# nivel0.net
KiCad netlist of a schematic drawn in EAGLE
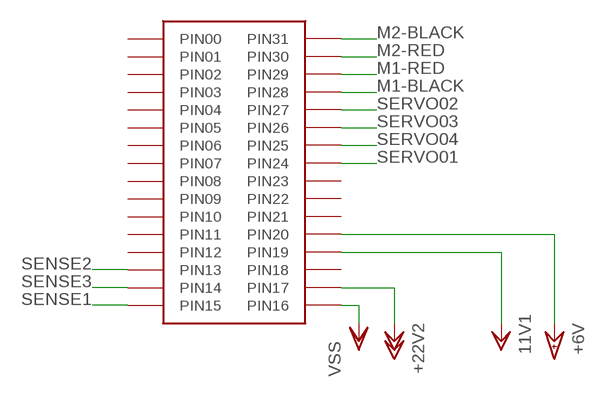
[diagram p0: schematic, sheet 1]
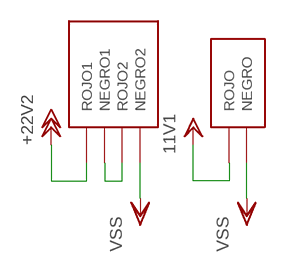
[diagram p1: schematic, sheet 2]
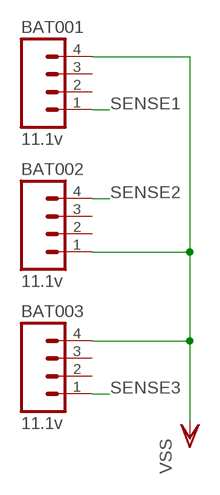
[diagram p2: schematic, sheet 3]
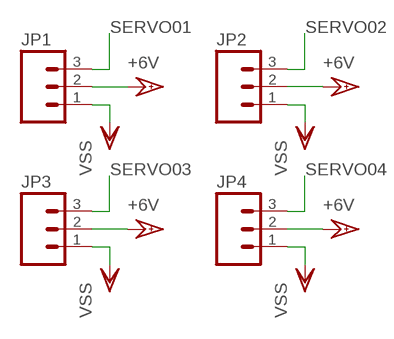
[diagram p3: schematic, sheet 4]
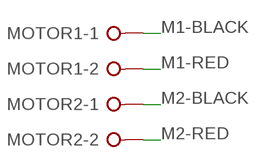
[diagram p4: schematic, sheet 5]

(export (version "E")
  (design (tool "Eeschema 10.0.6"))
  (components
    (comp (ref "U$11")
      (value "CONECTOR_AUDIO")
      (footprint "eagle-import:CONECTOR_AUDIO")
      (libsource (lib "eagle-import") (part "CONECTOR_AUDIO"))
    )
    (comp (ref "U$12")
      (value "CONECTOR_AUDIO2")
      (footprint "eagle-import:CONECTOR_AUDIO2")
      (libsource (lib "eagle-import") (part "CONECTOR_AUDIO2"))
    )
    (comp (ref "U$1")
      (value "BASE")
      (footprint "eagle-import:BASE")
      (libsource (lib "eagle-import") (part "BASE"))
    )
    (comp (ref "JP1")
      (value "M03LONGPADS")
      (footprint "eagle-import:1X03_LONGPADS")
      (libsource (lib "eagle-import") (part "M03LONGPADS"))
    )
    (comp (ref "JP2")
      (value "M03LONGPADS")
      (footprint "eagle-import:1X03_LONGPADS")
      (libsource (lib "eagle-import") (part "M03LONGPADS"))
    )
    (comp (ref "JP3")
      (value "M03LONGPADS")
      (footprint "eagle-import:1X03_LONGPADS")
      (libsource (lib "eagle-import") (part "M03LONGPADS"))
    )
    (comp (ref "JP4")
      (value "M03LONGPADS")
      (footprint "eagle-import:1X03_LONGPADS")
      (libsource (lib "eagle-import") (part "M03LONGPADS"))
    )
    (comp (ref "MOTOR1")
      (value "W237-02P")
      (footprint "eagle-import:W237-132")
      (libsource (lib "eagle-import") (part "W237-02P"))
    )
    (comp (ref "MOTOR2")
      (value "W237-02P")
      (footprint "eagle-import:W237-132")
      (libsource (lib "eagle-import") (part "W237-02P"))
    )
    (comp (ref "BAT001")
      (value "11.1v")
      (footprint "eagle-import:1X04_LONGPADS")
      (libsource (lib "eagle-import") (part "M04LONGPADS"))
    )
    (comp (ref "BAT002")
      (value "11.1v")
      (footprint "eagle-import:1X04_LONGPADS")
      (libsource (lib "eagle-import") (part "M04LONGPADS"))
    )
    (comp (ref "BAT003")
      (value "11.1v")
      (footprint "eagle-import:1X04_LONGPADS")
      (libsource (lib "eagle-import") (part "M04LONGPADS"))
    )
  )
  (nets
    (net (code "1") (name "+6V") (class "Default")
      (node (ref "JP1") (pin "2") (pinfunction "2_2") (pintype "passive"))
      (node (ref "JP2") (pin "2") (pinfunction "2_2") (pintype "passive"))
      (node (ref "JP3") (pin "2") (pinfunction "2_2") (pintype "passive"))
      (node (ref "JP4") (pin "2") (pinfunction "2_2") (pintype "passive"))
      (node (ref "U$1") (pin "PIN20") (pinfunction "PIN20_PIN20") (pintype "bidirectional"))
    )
    (net (code "2") (name "+11V1") (class "Default")
      (node (ref "U$1") (pin "PIN19") (pinfunction "PIN19_PIN19") (pintype "bidirectional"))
      (node (ref "U$12") (pin "P$2") (pinfunction "ROJO_P$2") (pintype "bidirectional"))
    )
    (net (code "3") (name "+22V") (class "Default")
      (node (ref "U$1") (pin "PIN17") (pinfunction "PIN17_PIN17") (pintype "bidirectional"))
      (node (ref "U$11") (pin "P$1") (pinfunction "ROJO1_P$1") (pintype "bidirectional"))
    )
    (net (code "4") (name "M1-BLACK") (class "Default")
      (node (ref "MOTOR1") (pin "1") (pinfunction "KL_1") (pintype "passive"))
      (node (ref "U$1") (pin "PIN28") (pinfunction "PIN28_PIN28") (pintype "bidirectional"))
    )
    (net (code "5") (name "M1-RED") (class "Default")
      (node (ref "MOTOR1") (pin "2") (pinfunction "KL_2") (pintype "passive"))
      (node (ref "U$1") (pin "PIN29") (pinfunction "PIN29_PIN29") (pintype "bidirectional"))
    )
    (net (code "6") (name "M2-BLACK") (class "Default")
      (node (ref "MOTOR2") (pin "1") (pinfunction "KL_1") (pintype "passive"))
      (node (ref "U$1") (pin "PIN31") (pinfunction "PIN31_PIN31") (pintype "bidirectional"))
    )
    (net (code "7") (name "M2-RED") (class "Default")
      (node (ref "MOTOR2") (pin "2") (pinfunction "KL_2") (pintype "passive"))
      (node (ref "U$1") (pin "PIN30") (pinfunction "PIN30_PIN30") (pintype "bidirectional"))
    )
    (net (code "8") (name "Net-(U$11-NEGRO1)") (class "Default")
      (node (ref "U$11") (pin "P$2") (pinfunction "NEGRO1_P$2") (pintype "bidirectional"))
      (node (ref "U$11") (pin "P$3") (pinfunction "ROJO2_P$3") (pintype "bidirectional"))
    )
    (net (code "9") (name "SENSE1") (class "Default")
      (node (ref "BAT001") (pin "1") (pinfunction "1_1") (pintype "passive"))
      (node (ref "U$1") (pin "PIN15") (pinfunction "PIN15_PIN15") (pintype "bidirectional"))
    )
    (net (code "10") (name "SENSE2") (class "Default")
      (node (ref "BAT002") (pin "4") (pinfunction "4_4") (pintype "passive"))
      (node (ref "U$1") (pin "PIN13") (pinfunction "PIN13_PIN13") (pintype "bidirectional"))
    )
    (net (code "11") (name "SENSE3") (class "Default")
      (node (ref "BAT003") (pin "1") (pinfunction "1_1") (pintype "passive"))
      (node (ref "U$1") (pin "PIN14") (pinfunction "PIN14_PIN14") (pintype "bidirectional"))
    )
    (net (code "12") (name "SERVO01") (class "Default")
      (node (ref "JP1") (pin "3") (pinfunction "3_3") (pintype "passive"))
      (node (ref "U$1") (pin "PIN24") (pinfunction "PIN24_PIN24") (pintype "bidirectional"))
    )
    (net (code "13") (name "SERVO02") (class "Default")
      (node (ref "JP2") (pin "3") (pinfunction "3_3") (pintype "passive"))
      (node (ref "U$1") (pin "PIN27") (pinfunction "PIN27_PIN27") (pintype "bidirectional"))
    )
    (net (code "14") (name "SERVO03") (class "Default")
      (node (ref "JP3") (pin "3") (pinfunction "3_3") (pintype "passive"))
      (node (ref "U$1") (pin "PIN26") (pinfunction "PIN26_PIN26") (pintype "bidirectional"))
    )
    (net (code "15") (name "SERVO04") (class "Default")
      (node (ref "JP4") (pin "3") (pinfunction "3_3") (pintype "passive"))
      (node (ref "U$1") (pin "PIN25") (pinfunction "PIN25_PIN25") (pintype "bidirectional"))
    )
    (net (code "16") (name "VSS") (class "Default")
      (node (ref "BAT001") (pin "4") (pinfunction "4_4") (pintype "passive"))
      (node (ref "BAT002") (pin "1") (pinfunction "1_1") (pintype "passive"))
      (node (ref "BAT003") (pin "4") (pinfunction "4_4") (pintype "passive"))
      (node (ref "JP1") (pin "1") (pinfunction "1_1") (pintype "passive"))
      (node (ref "JP2") (pin "1") (pinfunction "1_1") (pintype "passive"))
      (node (ref "JP3") (pin "1") (pinfunction "1_1") (pintype "passive"))
      (node (ref "JP4") (pin "1") (pinfunction "1_1") (pintype "passive"))
      (node (ref "U$1") (pin "PIN16") (pinfunction "PIN16_PIN16") (pintype "bidirectional"))
      (node (ref "U$11") (pin "P$4") (pinfunction "NEGRO2_P$4") (pintype "bidirectional"))
      (node (ref "U$12") (pin "P$1") (pinfunction "NEGRO_P$1") (pintype "bidirectional"))
    )
    (net (code "17") (name "unconnected-(BAT001-Pad2)") (class "Default")
      (node (ref "BAT001") (pin "2") (pinfunction "2_2") (pintype "passive"))
    )
    (net (code "18") (name "unconnected-(BAT001-Pad3)") (class "Default")
      (node (ref "BAT001") (pin "3") (pinfunction "3_3") (pintype "passive"))
    )
    (net (code "19") (name "unconnected-(BAT002-Pad2)") (class "Default")
      (node (ref "BAT002") (pin "2") (pinfunction "2_2") (pintype "passive"))
    )
    (net (code "20") (name "unconnected-(BAT002-Pad3)") (class "Default")
      (node (ref "BAT002") (pin "3") (pinfunction "3_3") (pintype "passive"))
    )
    (net (code "21") (name "unconnected-(BAT003-Pad2)") (class "Default")
      (node (ref "BAT003") (pin "2") (pinfunction "2_2") (pintype "passive"))
    )
    (net (code "22") (name "unconnected-(BAT003-Pad3)") (class "Default")
      (node (ref "BAT003") (pin "3") (pinfunction "3_3") (pintype "passive"))
    )
    (net (code "23") (name "unconnected-(U$1-PadPIN00)") (class "Default")
      (node (ref "U$1") (pin "PIN00") (pinfunction "PIN00_PIN00") (pintype "bidirectional"))
    )
    (net (code "24") (name "unconnected-(U$1-PadPIN01)") (class "Default")
      (node (ref "U$1") (pin "PIN01") (pinfunction "PIN01_PIN01") (pintype "bidirectional"))
    )
    (net (code "25") (name "unconnected-(U$1-PadPIN02)") (class "Default")
      (node (ref "U$1") (pin "PIN02") (pinfunction "PIN02_PIN02") (pintype "bidirectional"))
    )
    (net (code "26") (name "unconnected-(U$1-PadPIN03)") (class "Default")
      (node (ref "U$1") (pin "PIN03") (pinfunction "PIN03_PIN03") (pintype "bidirectional"))
    )
    (net (code "27") (name "unconnected-(U$1-PadPIN04)") (class "Default")
      (node (ref "U$1") (pin "PIN04") (pinfunction "PIN04_PIN04") (pintype "bidirectional"))
    )
    (net (code "28") (name "unconnected-(U$1-PadPIN05)") (class "Default")
      (node (ref "U$1") (pin "PIN05") (pinfunction "PIN05_PIN05") (pintype "bidirectional"))
    )
    (net (code "29") (name "unconnected-(U$1-PadPIN06)") (class "Default")
      (node (ref "U$1") (pin "PIN06") (pinfunction "PIN06_PIN06") (pintype "bidirectional"))
    )
    (net (code "30") (name "unconnected-(U$1-PadPIN07)") (class "Default")
      (node (ref "U$1") (pin "PIN07") (pinfunction "PIN07_PIN07") (pintype "bidirectional"))
    )
    (net (code "31") (name "unconnected-(U$1-PadPIN08)") (class "Default")
      (node (ref "U$1") (pin "PIN08") (pinfunction "PIN08_PIN08") (pintype "bidirectional"))
    )
    (net (code "32") (name "unconnected-(U$1-PadPIN09)") (class "Default")
      (node (ref "U$1") (pin "PIN09") (pinfunction "PIN09_PIN09") (pintype "bidirectional"))
    )
    (net (code "33") (name "unconnected-(U$1-PadPIN10)") (class "Default")
      (node (ref "U$1") (pin "PIN10") (pinfunction "PIN10_PIN10") (pintype "bidirectional"))
    )
    (net (code "34") (name "unconnected-(U$1-PadPIN11)") (class "Default")
      (node (ref "U$1") (pin "PIN11") (pinfunction "PIN11_PIN11") (pintype "bidirectional"))
    )
    (net (code "35") (name "unconnected-(U$1-PadPIN12)") (class "Default")
      (node (ref "U$1") (pin "PIN12") (pinfunction "PIN12_PIN12") (pintype "bidirectional"))
    )
    (net (code "36") (name "unconnected-(U$1-PadPIN18)") (class "Default")
      (node (ref "U$1") (pin "PIN18") (pinfunction "PIN18_PIN18") (pintype "bidirectional"))
    )
    (net (code "37") (name "unconnected-(U$1-PadPIN21)") (class "Default")
      (node (ref "U$1") (pin "PIN21") (pinfunction "PIN21_PIN21") (pintype "bidirectional"))
    )
    (net (code "38") (name "unconnected-(U$1-PadPIN22)") (class "Default")
      (node (ref "U$1") (pin "PIN22") (pinfunction "PIN22_PIN22") (pintype "bidirectional"))
    )
    (net (code "39") (name "unconnected-(U$1-PadPIN23)") (class "Default")
      (node (ref "U$1") (pin "PIN23") (pinfunction "PIN23_PIN23") (pintype "bidirectional"))
    )
  )
)
